# energy_harvesting.net
KiCad netlist of a schematic drawn in Altium Designer
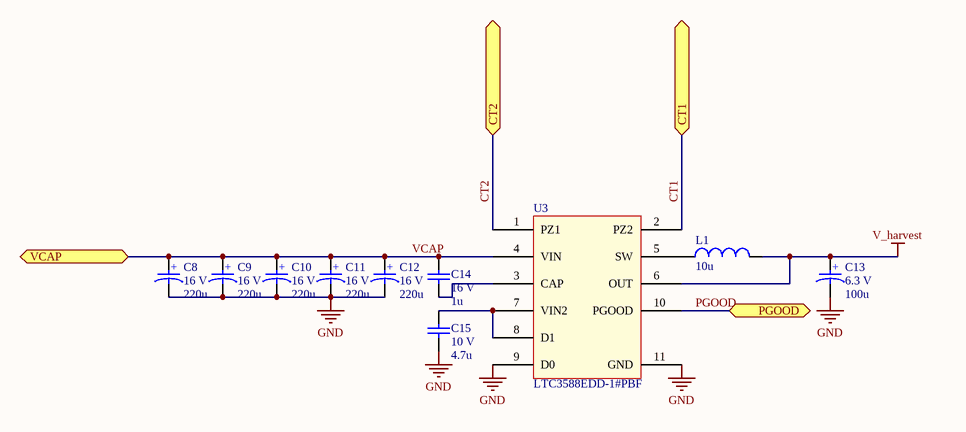
[diagram p0: energy_harvesting.SchDoc]

(export (version "E")
  (design (tool "Eeschema 10.0.6"))
  (components
    (comp (ref "C8")
      (value "220u")
      (footprint "2917")
      (description "220µF ±10% Molded Tantalum Capacitors 16V")
      (fields
        (field (name "TOLERANCE") "10%")
        (field (name "VOLTAGE RATED") "16 V")
        (field (name "MANUFACTURER PART NUMBER") "T495X227K016ATE100")
      )
      (libsource (lib "capacitors") (part "T495X227K016ATE100"))
    )
    (comp (ref "C9")
      (value "220u")
      (footprint "2917")
      (description "220µF ±10% Molded Tantalum Capacitors 16V")
      (fields
        (field (name "TOLERANCE") "10%")
        (field (name "VOLTAGE RATED") "16 V")
        (field (name "MANUFACTURER PART NUMBER") "T495X227K016ATE100")
      )
      (libsource (lib "capacitors") (part "T495X227K016ATE100"))
    )
    (comp (ref "C10")
      (value "220u")
      (footprint "2917")
      (description "220µF ±10% Molded Tantalum Capacitors 16V")
      (fields
        (field (name "TOLERANCE") "10%")
        (field (name "VOLTAGE RATED") "16 V")
        (field (name "MANUFACTURER PART NUMBER") "T495X227K016ATE100")
      )
      (libsource (lib "capacitors") (part "T495X227K016ATE100"))
    )
    (comp (ref "C11")
      (value "220u")
      (footprint "2917")
      (description "220µF ±10% Molded Tantalum Capacitors 16V")
      (fields
        (field (name "TOLERANCE") "10%")
        (field (name "VOLTAGE RATED") "16 V")
        (field (name "MANUFACTURER PART NUMBER") "T495X227K016ATE100")
      )
      (libsource (lib "capacitors") (part "T495X227K016ATE100"))
    )
    (comp (ref "C12")
      (value "220u")
      (footprint "2917")
      (description "220µF ±10% Molded Tantalum Capacitors 16V")
      (fields
        (field (name "TOLERANCE") "10%")
        (field (name "VOLTAGE RATED") "16 V")
        (field (name "MANUFACTURER PART NUMBER") "T495X227K016ATE100")
      )
      (libsource (lib "capacitors") (part "T495X227K016ATE100"))
    )
    (comp (ref "C13")
      (value "100u")
      (footprint "1206 - POLAR MARKING")
      (description "100µF ±20% Molded Tantalum Capacitors 6.3V 1206")
      (fields
        (field (name "VOLTAGE RATED") "6.3 V")
        (field (name "TOLERANCE") "20%")
        (field (name "MANUFACTURER PART NUMBER") "F930J107MAA")
      )
      (libsource (lib "capacitors") (part "F930J107MAA"))
    )
    (comp (ref "C14")
      (value "1u")
      (footprint "0603")
      (description "1µF ±10% 16V Ceramic Capacitor X7R 0603")
      (fields
        (field (name "VOLTAGE RATED") "16 V")
        (field (name "TOLERANCE") "10%")
        (field (name "MANUFACTURER PART NUMBER") "C1608X7R1C105K080AC")
      )
      (libsource (lib "capacitors") (part "C1608X7R1C105K080AC"))
    )
    (comp (ref "C15")
      (value "4.7u")
      (footprint "0603")
      (description "4.7µF ±10% 10V Ceramic Capacitor X5R 0603")
      (fields
        (field (name "TOLERANCE") "10%")
        (field (name "VOLTAGE RATED") "10 V")
        (field (name "MANUFACTURER PART NUMBER") "CGB3B1X5R1A475K055AC")
      )
      (libsource (lib "capacitors") (part "CGB3B1X5R1A475K055AC"))
    )
    (comp (ref "L1")
      (value "10u")
      (footprint "CDRH2D18")
      (description "10µH Shielded Inductor 1A 180 mOhm Max Nonstandard")
      (fields
        (field (name "TOLERANCE") "30%")
        (field (name "MANUFACTURER PART NUMBER") "CDRH2D18/LDNP-100NC")
      )
      (libsource (lib "inductors") (part "CDRH2D18/LDNP-100NC"))
    )
    (comp (ref "U3")
      (value "LTC3588EDD-1#PBF")
      (footprint "QFN-10")
      (description "Piezoelectric Energy Harvesting Power Supply")
      (libsource (lib "voltage regulator") (part "LTC3588EDD-1#PBF"))
    )
  )
  (nets
    (net (code "1") (name "/CT1") (class "Default")
      (node (ref "U3") (pin "2") (pinfunction "PZ2_2") (pintype "passive"))
    )
    (net (code "2") (name "/CT2") (class "Default")
      (node (ref "U3") (pin "1") (pinfunction "PZ1_1") (pintype "passive"))
    )
    (net (code "3") (name "/PGOOD") (class "Default")
      (node (ref "U3") (pin "10") (pinfunction "PGOOD_10") (pintype "passive"))
    )
    (net (code "4") (name "/VCAP") (class "Default")
      (node (ref "C10") (pin "1") (pintype "passive"))
      (node (ref "C11") (pin "1") (pintype "passive"))
      (node (ref "C12") (pin "1") (pintype "passive"))
      (node (ref "C14") (pin "1") (pintype "passive"))
      (node (ref "C8") (pin "1") (pintype "passive"))
      (node (ref "C9") (pin "1") (pintype "passive"))
      (node (ref "U3") (pin "4") (pinfunction "VIN_4") (pintype "passive"))
    )
    (net (code "5") (name "GND") (class "Default")
      (node (ref "C10") (pin "2") (pintype "passive"))
      (node (ref "C11") (pin "2") (pintype "passive"))
      (node (ref "C12") (pin "2") (pintype "passive"))
      (node (ref "C13") (pin "2") (pintype "passive"))
      (node (ref "C15") (pin "2") (pintype "passive"))
      (node (ref "C8") (pin "2") (pintype "passive"))
      (node (ref "C9") (pin "2") (pintype "passive"))
      (node (ref "U3") (pin "11") (pinfunction "GND_11") (pintype "passive"))
      (node (ref "U3") (pin "9") (pinfunction "D0_9") (pintype "passive"))
    )
    (net (code "6") (name "Net-(U3-CAP)") (class "Default")
      (node (ref "C14") (pin "2") (pintype "passive"))
      (node (ref "U3") (pin "3") (pinfunction "CAP_3") (pintype "passive"))
    )
    (net (code "7") (name "Net-(U3-D1)") (class "Default")
      (node (ref "C15") (pin "1") (pintype "passive"))
      (node (ref "U3") (pin "7") (pinfunction "VIN2_7") (pintype "passive"))
      (node (ref "U3") (pin "8") (pinfunction "D1_8") (pintype "passive"))
    )
    (net (code "8") (name "Net-(U3-SW)") (class "Default")
      (node (ref "L1") (pin "2") (pintype "passive"))
      (node (ref "U3") (pin "5") (pinfunction "SW_5") (pintype "passive"))
    )
    (net (code "9") (name "V_harvest") (class "Default")
      (node (ref "C13") (pin "1") (pintype "passive"))
      (node (ref "L1") (pin "1") (pintype "passive"))
      (node (ref "U3") (pin "6") (pinfunction "OUT_6") (pintype "passive"))
    )
  )
)
